# 1_Power_Path.net
KiCad netlist of a schematic drawn in Altium Designer
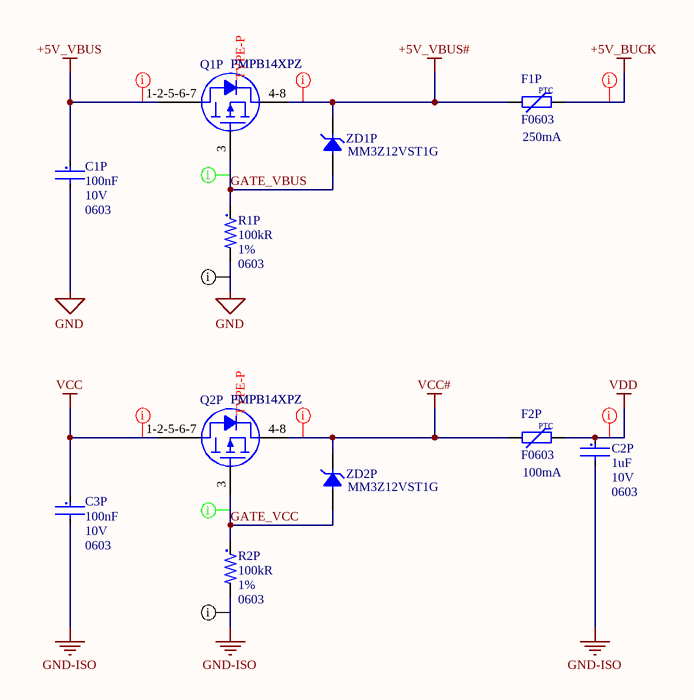
[diagram p0: 1_Power_Path.SchDoc]

(export (version "E")
  (design (tool "Eeschema 10.0.6"))
  (components
    (comp (ref "C1P")
      (value "100nF")
      (footprint "C0603-IPC_C_No_Silk")
      (description "Multilayer Ceramic Capacitor, 0.1 uF, 10 V, ± 10%, X7R, 0603 [1608 Metric]")
      (fields
        (field (name "MANUFACTURER PART NUMBER") "C0603C104K8RACTU")
        (field (name "MANUFACTURER") "KEMET")
        (field (name "VOLTAGE") "10V")
        (field (name "CASE/PACKAGE") "0603")
      )
      (libsource (lib "Lib_Capacitor_0603") (part "100nF_10V"))
    )
    (comp (ref "C2P")
      (value "1uF")
      (footprint "C0603-IPC_C_No_Silk")
      (description "Ceramic Capacitor, Multilayer, Ceramic, 10V, 10% +Tol, 10% -Tol, X5R, 15% TC, 1uF, 0603")
      (fields
        (field (name "MANUFACTURER") "KEMET")
        (field (name "MANUFACTURER PART NUMBER") "C0603C105K8PACTU")
        (field (name "VOLTAGE RATING") "10V")
        (field (name "CASE CODE (IMPERIAL)") "0603")
      )
      (libsource (lib "Lib_Capacitor_0603") (part "1uF_10V"))
    )
    (comp (ref "C3P")
      (value "100nF")
      (footprint "C0603-IPC_C_No_Silk")
      (description "Multilayer Ceramic Capacitor, 0.1 uF, 10 V, ± 10%, X7R, 0603 [1608 Metric]")
      (fields
        (field (name "MANUFACTURER PART NUMBER") "C0603C104K8RACTU")
        (field (name "MANUFACTURER") "KEMET")
        (field (name "VOLTAGE") "10V")
        (field (name "CASE/PACKAGE") "0603")
      )
      (libsource (lib "Lib_Capacitor_0603") (part "100nF_10V"))
    )
    (comp (ref "F1P")
      (value "F0603")
      (footprint "R0603-MFG")
      (description "Fuse PPTC SMD 0603")
      (fields (field (name "ALTIUM_VALUE") "250mA"))
      (libsource (lib "Lib_Fuse") (part "FUSE_PPTC_0603"))
    )
    (comp (ref "F2P")
      (value "F0603")
      (footprint "R0603-MFG")
      (description "Fuse PPTC SMD 0603")
      (fields (field (name "ALTIUM_VALUE") "100mA"))
      (libsource (lib "Lib_Fuse") (part "FUSE_PPTC_0603"))
    )
    (comp (ref "Q1P")
      (value "PMPB14XPZ")
      (footprint "DFN2020MD-MFG")
      (fields (field (name "MANUFACTURER") "Nexperia") (field (name "MANUFACTURER PART NUMBER") "PMPB14XPZ"))
      (libsource (lib "Lib_Mosfet_PNP") (part "PMPB14XPZ"))
    )
    (comp (ref "Q2P")
      (value "PMPB14XPZ")
      (footprint "DFN2020MD-MFG")
      (fields (field (name "MANUFACTURER") "Nexperia") (field (name "MANUFACTURER PART NUMBER") "PMPB14XPZ"))
      (libsource (lib "Lib_Mosfet_PNP") (part "PMPB14XPZ"))
    )
    (comp (ref "R1P")
      (value "100kR")
      (footprint "R0603-MFG")
      (description "SMD Chip Resistor, 100 kOhm, ± 1%, 100 mW, 0603 [1608 Metric], Thick Film, General Purpose")
      (fields
        (field (name "MANUFACTURER") "Yageo")
        (field (name "MANUFACTURER PART NUMBER") "AC0603FR-07100KL")
        (field (name "TOLERANCE") "1%")
        (field (name "CASE/PACKAGE") "0603")
      )
      (libsource (lib "Lib_Register_0603") (part "100K"))
    )
    (comp (ref "R2P")
      (value "100kR")
      (footprint "R0603-MFG")
      (description "SMD Chip Resistor, 100 kOhm, ± 1%, 100 mW, 0603 [1608 Metric], Thick Film, General Purpose")
      (fields
        (field (name "MANUFACTURER") "Yageo")
        (field (name "MANUFACTURER PART NUMBER") "AC0603FR-07100KL")
        (field (name "TOLERANCE") "1%")
        (field (name "CASE/PACKAGE") "0603")
      )
      (libsource (lib "Lib_Register_0603") (part "100K"))
    )
    (comp (ref "ZD1P")
      (value "MM3Z12VST1G")
      (footprint "SOD-323")
      (description "MM3Z12VST1G Zener Diode, 12V 2% 200 mW SMT 2-Pin SOD-323 ¦ ON Semiconductor MM3Z12VST1G")
      (fields (field (name "MANUFACTURER") "ON Semiconductor") (field (name "TOLERANCE") "2%"))
      (libsource (lib "Lib_Diodes") (part "MM3Z12VST1G"))
    )
    (comp (ref "ZD2P")
      (value "MM3Z12VST1G")
      (footprint "SOD-323")
      (description "MM3Z12VST1G Zener Diode, 12V 2% 200 mW SMT 2-Pin SOD-323 ¦ ON Semiconductor MM3Z12VST1G")
      (fields (field (name "MANUFACTURER") "ON Semiconductor") (field (name "TOLERANCE") "2%"))
      (libsource (lib "Lib_Diodes") (part "MM3Z12VST1G"))
    )
  )
  (nets
    (net (code "1") (name "+5V_BUCK") (class "Default")
      (node (ref "F1P") (pin "2") (pinfunction "2_2") (pintype "passive"))
    )
    (net (code "2") (name "+5V_VBUS") (class "Default")
      (node (ref "C1P") (pin "1") (pinfunction "1_1") (pintype "passive"))
      (node (ref "Q1P") (pin "1-2-5-6-7") (pinfunction "D_1-2-5-6-7") (pintype "passive"))
    )
    (net (code "3") (name "+5V_VBUS#") (class "Default")
      (node (ref "F1P") (pin "1") (pinfunction "1_1") (pintype "passive"))
      (node (ref "Q1P") (pin "4-8") (pinfunction "S_4-8") (pintype "passive"))
      (node (ref "ZD1P") (pin "1") (pinfunction "C_1") (pintype "passive"))
    )
    (net (code "4") (name "/GATE_VBUS") (class "Default")
      (node (ref "Q1P") (pin "3") (pinfunction "G_3") (pintype "passive"))
      (node (ref "R1P") (pin "1") (pinfunction "1_1") (pintype "passive"))
      (node (ref "ZD1P") (pin "2") (pinfunction "A_2") (pintype "passive"))
    )
    (net (code "5") (name "/GATE_VCC") (class "Default")
      (node (ref "Q2P") (pin "3") (pinfunction "G_3") (pintype "passive"))
      (node (ref "R2P") (pin "1") (pinfunction "1_1") (pintype "passive"))
      (node (ref "ZD2P") (pin "2") (pinfunction "A_2") (pintype "passive"))
    )
    (net (code "6") (name "GND") (class "Default")
      (node (ref "C1P") (pin "2") (pinfunction "2_2") (pintype "passive"))
      (node (ref "R1P") (pin "2") (pinfunction "2_2") (pintype "passive"))
    )
    (net (code "7") (name "GND-ISO") (class "Default")
      (node (ref "C2P") (pin "2") (pinfunction "2_2") (pintype "passive"))
      (node (ref "C3P") (pin "2") (pinfunction "2_2") (pintype "passive"))
      (node (ref "R2P") (pin "2") (pinfunction "2_2") (pintype "passive"))
    )
    (net (code "8") (name "VCC") (class "Default")
      (node (ref "C3P") (pin "1") (pinfunction "1_1") (pintype "passive"))
      (node (ref "Q2P") (pin "1-2-5-6-7") (pinfunction "D_1-2-5-6-7") (pintype "passive"))
    )
    (net (code "9") (name "VCC#") (class "Default")
      (node (ref "F2P") (pin "1") (pinfunction "1_1") (pintype "passive"))
      (node (ref "Q2P") (pin "4-8") (pinfunction "S_4-8") (pintype "passive"))
      (node (ref "ZD2P") (pin "1") (pinfunction "C_1") (pintype "passive"))
    )
    (net (code "10") (name "VDD") (class "Default")
      (node (ref "C2P") (pin "1") (pinfunction "1_1") (pintype "passive"))
      (node (ref "F2P") (pin "2") (pinfunction "2_2") (pintype "passive"))
    )
  )
)
